# DSO_Trig.net
KiCad netlist of a schematic drawn in Altium Designer
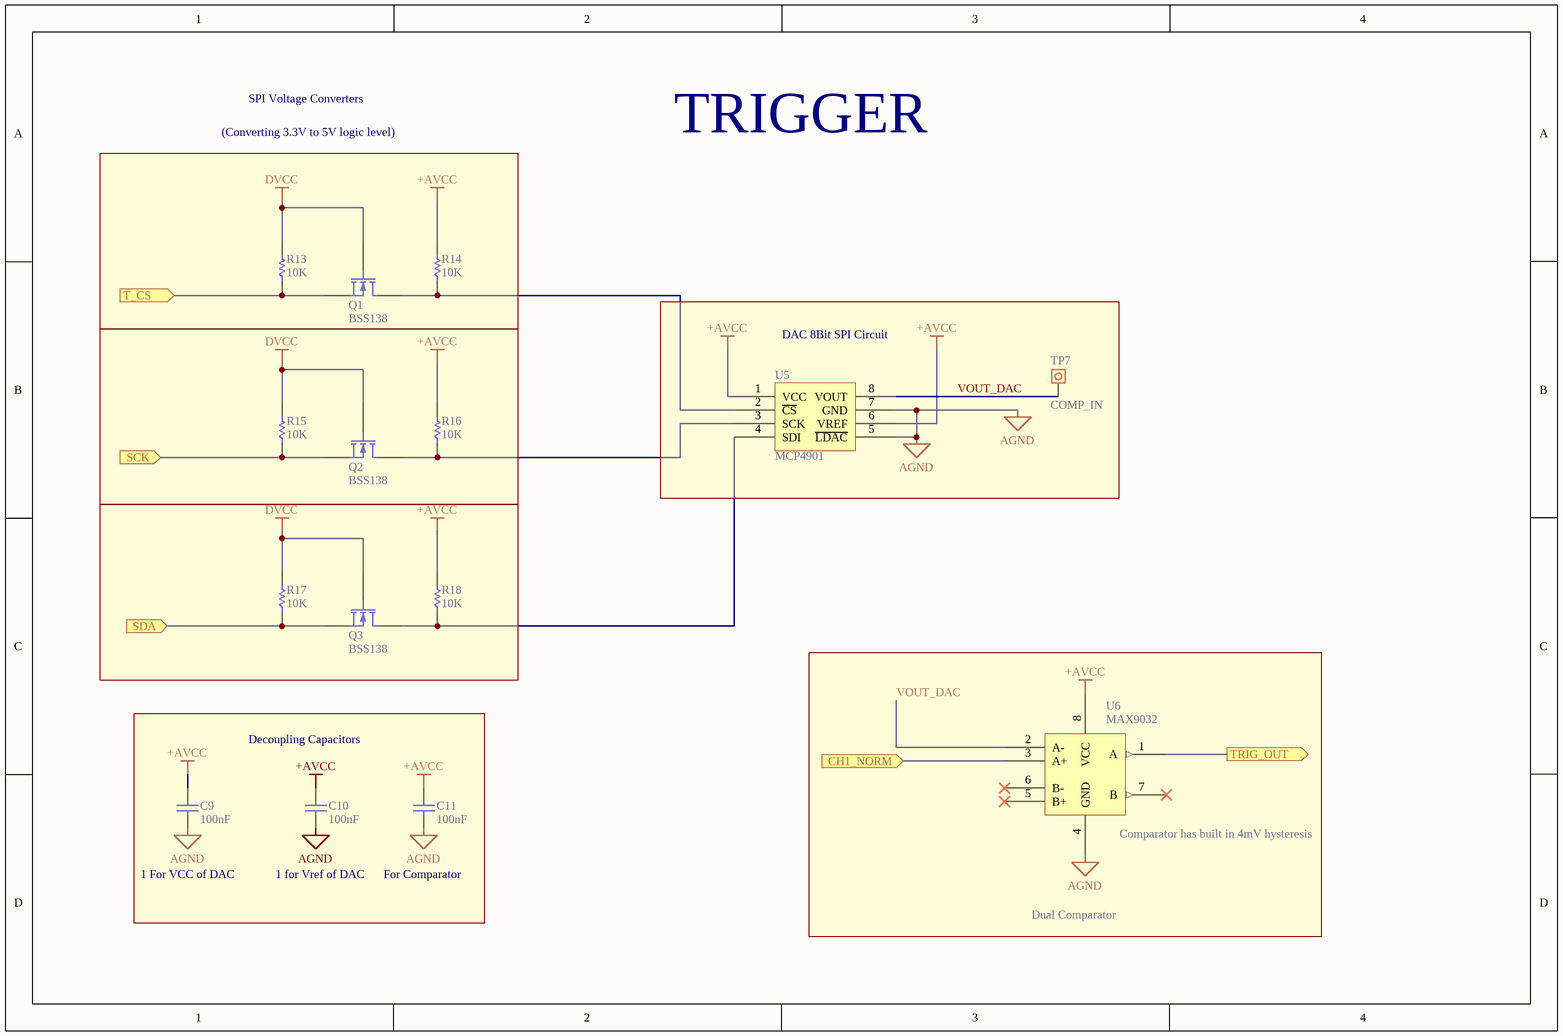
[diagram p0: DSO_Trig.SchDoc]

(export (version "E")
  (design (tool "Eeschema 10.0.6"))
  (components
    (comp (ref "C9")
      (value "100nF")
      (footprint "0805C")
      (description "Capacitor")
      (fields (field (name "REVIEWED BY") "RM - 2018/08/05"))
      (libsource (lib "DSO") (part "C"))
    )
    (comp (ref "C10")
      (value "100nF")
      (footprint "0805C")
      (description "Capacitor")
      (fields (field (name "REVIEWED BY") "RM - 2018/08/05"))
      (libsource (lib "DSO") (part "C"))
    )
    (comp (ref "C11")
      (value "100nF")
      (footprint "0805C")
      (description "Capacitor")
      (fields (field (name "REVIEWED BY") "RM - 2018/08/05"))
      (libsource (lib "DSO") (part "C"))
    )
    (comp (ref "Q1")
      (value "BSS138")
      (footprint "SOT23")
      (description "N-Channel MOSFET")
      (fields (field (name "PUBLISHER") "Altium Limited"))
      (libsource (lib "DSO") (part "MOSFET-N"))
    )
    (comp (ref "Q2")
      (value "BSS138")
      (footprint "SOT23")
      (description "N-Channel MOSFET")
      (fields (field (name "PUBLISHER") "Altium Limited"))
      (libsource (lib "DSO") (part "MOSFET-N"))
    )
    (comp (ref "Q3")
      (value "BSS138")
      (footprint "SOT23")
      (description "N-Channel MOSFET")
      (fields (field (name "PUBLISHER") "Altium Limited"))
      (libsource (lib "DSO") (part "MOSFET-N"))
    )
    (comp (ref "R13")
      (value "10K")
      (footprint "0805")
      (description "Resistor")
      (fields (field (name "REVIEWED BY") "RM - 2018/08/05"))
      (libsource (lib "DSO") (part "R"))
    )
    (comp (ref "R14")
      (value "10K")
      (footprint "0805")
      (description "Resistor")
      (fields (field (name "REVIEWED BY") "RM - 2018/08/05"))
      (libsource (lib "DSO") (part "R"))
    )
    (comp (ref "R15")
      (value "10K")
      (footprint "0805")
      (description "Resistor")
      (fields (field (name "REVIEWED BY") "RM - 2018/08/05"))
      (libsource (lib "DSO") (part "R"))
    )
    (comp (ref "R16")
      (value "10K")
      (footprint "0805")
      (description "Resistor")
      (fields (field (name "REVIEWED BY") "RM - 2018/08/05"))
      (libsource (lib "DSO") (part "R"))
    )
    (comp (ref "R17")
      (value "10K")
      (footprint "0805")
      (description "Resistor")
      (fields (field (name "REVIEWED BY") "RM - 2018/08/05"))
      (libsource (lib "DSO") (part "R"))
    )
    (comp (ref "R18")
      (value "10K")
      (footprint "0805")
      (description "Resistor")
      (fields (field (name "REVIEWED BY") "RM - 2018/08/05"))
      (libsource (lib "DSO") (part "R"))
    )
    (comp (ref "TP7")
      (value "COMP_IN")
      (footprint "Testpoin")
      (description "Pad")
      (fields (field (name "Comment") "INPUT"))
      (libsource (lib "DSO") (part "Test Point"))
    )
    (comp (ref "U5")
      (value "MCP4901")
      (footprint "SOIC-8")
      (description "DAC 8bit SPI")
      (fields (field (name "REVIEWED BY") "RM - 2018/08/05"))
      (libsource (lib "DSO") (part "MCP4901"))
    )
    (comp (ref "U6")
      (value "MAX9032")
      (footprint "SOIC-8")
      (description "Dual Comparator")
      (fields (field (name "REVIEWED BY") "RM - 2018/08/05"))
      (libsource (lib "DSO") (part "MAX9032"))
    )
  )
  (nets
    (net (code "1") (name "+AVCC") (class "Default")
      (node (ref "C10") (pin "1") (pinfunction "1_1") (pintype "passive"))
      (node (ref "C11") (pin "1") (pinfunction "1_1") (pintype "passive"))
      (node (ref "C9") (pin "1") (pinfunction "1_1") (pintype "passive"))
      (node (ref "R14") (pin "2") (pintype "passive"))
      (node (ref "R16") (pin "2") (pintype "passive"))
      (node (ref "R18") (pin "2") (pintype "passive"))
      (node (ref "U5") (pin "1") (pinfunction "VCC_1") (pintype "passive"))
      (node (ref "U5") (pin "6") (pinfunction "VREF_6") (pintype "passive"))
      (node (ref "U6") (pin "8") (pinfunction "VCC_8") (pintype "passive"))
    )
    (net (code "2") (name "/CH1_NORM") (class "Default")
      (node (ref "U6") (pin "3") (pinfunction "A+_3") (pintype "passive"))
    )
    (net (code "3") (name "/SCK") (class "Default")
      (node (ref "Q2") (pin "2") (pinfunction "2_2") (pintype "passive"))
      (node (ref "R15") (pin "1") (pintype "passive"))
    )
    (net (code "4") (name "/SDA") (class "Default")
      (node (ref "Q3") (pin "2") (pinfunction "2_2") (pintype "passive"))
      (node (ref "R17") (pin "1") (pintype "passive"))
    )
    (net (code "5") (name "/TRIG_OUT") (class "Default")
      (node (ref "U6") (pin "1") (pinfunction "A_1") (pintype "output"))
    )
    (net (code "6") (name "/T_CS") (class "Default")
      (node (ref "Q1") (pin "2") (pinfunction "2_2") (pintype "passive"))
      (node (ref "R13") (pin "1") (pintype "passive"))
    )
    (net (code "7") (name "/VOUT_DAC") (class "Default")
      (node (ref "TP7") (pin "1") (pintype "passive"))
      (node (ref "U5") (pin "8") (pinfunction "VOUT_8") (pintype "passive"))
      (node (ref "U6") (pin "2") (pinfunction "A-_2") (pintype "passive"))
    )
    (net (code "8") (name "AGND") (class "Default")
      (node (ref "C10") (pin "2") (pinfunction "2_2") (pintype "passive"))
      (node (ref "C11") (pin "2") (pinfunction "2_2") (pintype "passive"))
      (node (ref "C9") (pin "2") (pinfunction "2_2") (pintype "passive"))
      (node (ref "U5") (pin "5") (pinfunction "~{LDAC}_5") (pintype "passive"))
      (node (ref "U5") (pin "7") (pinfunction "GND_7") (pintype "passive"))
      (node (ref "U6") (pin "4") (pinfunction "GND_4") (pintype "passive"))
    )
    (net (code "9") (name "DVCC") (class "Default")
      (node (ref "Q1") (pin "1") (pinfunction "1_1") (pintype "passive"))
      (node (ref "Q2") (pin "1") (pinfunction "1_1") (pintype "passive"))
      (node (ref "Q3") (pin "1") (pinfunction "1_1") (pintype "passive"))
      (node (ref "R13") (pin "2") (pintype "passive"))
      (node (ref "R15") (pin "2") (pintype "passive"))
      (node (ref "R17") (pin "2") (pintype "passive"))
    )
    (net (code "10") (name "Net-(U5-SCK)") (class "Default")
      (node (ref "Q2") (pin "3") (pinfunction "3_3") (pintype "passive"))
      (node (ref "R16") (pin "1") (pintype "passive"))
      (node (ref "U5") (pin "3") (pinfunction "SCK_3") (pintype "passive"))
    )
    (net (code "11") (name "Net-(U5-SDI)") (class "Default")
      (node (ref "Q3") (pin "3") (pinfunction "3_3") (pintype "passive"))
      (node (ref "R18") (pin "1") (pintype "passive"))
      (node (ref "U5") (pin "4") (pinfunction "SDI_4") (pintype "passive"))
    )
    (net (code "12") (name "Net-(U5-~{CS})") (class "Default")
      (node (ref "Q1") (pin "3") (pinfunction "3_3") (pintype "passive"))
      (node (ref "R14") (pin "1") (pintype "passive"))
      (node (ref "U5") (pin "2") (pinfunction "~{CS}_2") (pintype "passive"))
    )
    (net (code "13") (name "unconnected-(U6-B+-Pad5)") (class "Default")
      (node (ref "U6") (pin "5") (pinfunction "B+_5") (pintype "passive+no_connect"))
    )
    (net (code "14") (name "unconnected-(U6-B--Pad6)") (class "Default")
      (node (ref "U6") (pin "6") (pinfunction "B-_6") (pintype "passive+no_connect"))
    )
    (net (code "15") (name "unconnected-(U6-B-Pad7)") (class "Default")
      (node (ref "U6") (pin "7") (pinfunction "B_7") (pintype "output+no_connect"))
    )
  )
)
